# 1.net
KiCad netlist of a schematic drawn in Altium Designer
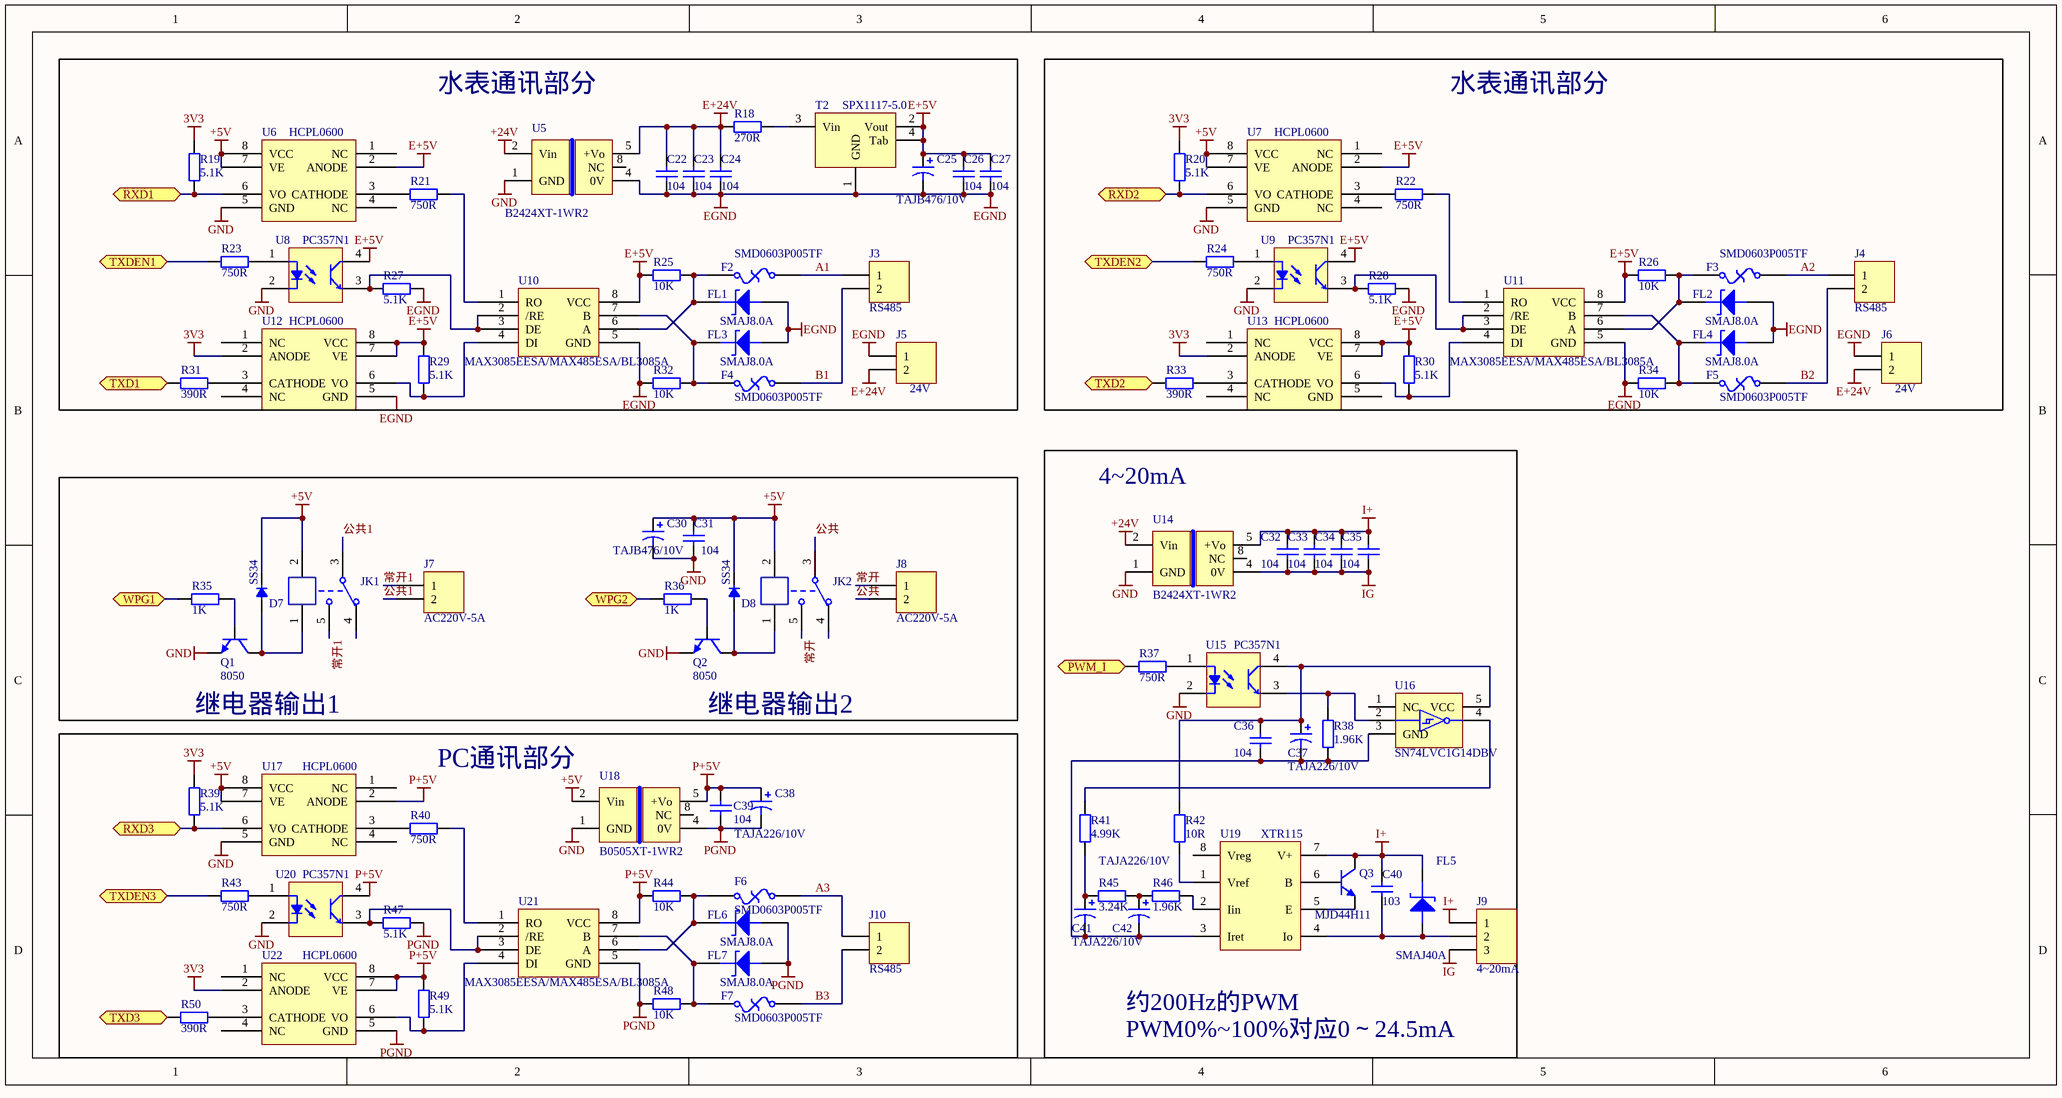
[diagram p0: 通讯部分(1).SchDoc]

(export (version "E")
  (design (tool "Eeschema 10.0.6"))
  (components
    (comp (ref "C22")
      (value "104")
      (footprint "C 0603_M")
      (description "Capacitor (Semiconductor SIM Model)")
      (fields (field (name "PUBLISHER") "Altium Limited"))
      (libsource (lib "*") (part "Cap Semi"))
    )
    (comp (ref "C23")
      (value "104")
      (footprint "C 0603_M")
      (description "Capacitor (Semiconductor SIM Model)")
      (fields (field (name "PUBLISHER") "Altium Limited"))
      (libsource (lib "*") (part "Cap Semi"))
    )
    (comp (ref "C24")
      (value "104")
      (footprint "C 0603_M")
      (description "Capacitor (Semiconductor SIM Model)")
      (fields (field (name "PUBLISHER") "Altium Limited"))
      (libsource (lib "*") (part "Cap Semi"))
    )
    (comp (ref "C25")
      (value "TAJB476/10V")
      (footprint "3528")
      (description "Polarized Capacitor (Radial)")
      (fields (field (name "PUBLISHER") "Altium Limited"))
      (libsource (lib "*") (part "Cap Pol1"))
    )
    (comp (ref "C26")
      (value "104")
      (footprint "C 0603_M")
      (description "Capacitor (Semiconductor SIM Model)")
      (fields (field (name "PUBLISHER") "Altium Limited"))
      (libsource (lib "*") (part "Cap Semi"))
    )
    (comp (ref "C27")
      (value "104")
      (footprint "C 0603_M")
      (description "Capacitor (Semiconductor SIM Model)")
      (fields (field (name "PUBLISHER") "Altium Limited"))
      (libsource (lib "*") (part "Cap Semi"))
    )
    (comp (ref "C30")
      (value "TAJB476/10V")
      (footprint "3528")
      (description "Polarized Capacitor (Radial)")
      (fields (field (name "PUBLISHER") "Altium Limited"))
      (libsource (lib "*") (part "Cap Pol1"))
    )
    (comp (ref "C31")
      (value "104")
      (footprint "C 0603_M")
      (description "Capacitor (Semiconductor SIM Model)")
      (fields (field (name "PUBLISHER") "Altium Limited"))
      (libsource (lib "*") (part "Cap Semi"))
    )
    (comp (ref "C32")
      (value "104")
      (footprint "C 0603_M")
      (description "Capacitor (Semiconductor SIM Model)")
      (fields (field (name "PUBLISHER") "Altium Limited"))
      (libsource (lib "*") (part "Cap Semi"))
    )
    (comp (ref "C33")
      (value "104")
      (footprint "C 0603_M")
      (description "Capacitor (Semiconductor SIM Model)")
      (fields (field (name "PUBLISHER") "Altium Limited"))
      (libsource (lib "*") (part "Cap Semi"))
    )
    (comp (ref "C34")
      (value "104")
      (footprint "C 0603_M")
      (description "Capacitor (Semiconductor SIM Model)")
      (fields (field (name "PUBLISHER") "Altium Limited"))
      (libsource (lib "*") (part "Cap Semi"))
    )
    (comp (ref "C35")
      (value "104")
      (footprint "C 0603_M")
      (description "Capacitor (Semiconductor SIM Model)")
      (fields (field (name "PUBLISHER") "Altium Limited"))
      (libsource (lib "*") (part "Cap Semi"))
    )
    (comp (ref "C36")
      (value "104")
      (footprint "C 0603_M")
      (description "Capacitor (Semiconductor SIM Model)")
      (fields (field (name "PUBLISHER") "Altium Limited"))
      (libsource (lib "*") (part "Cap Semi"))
    )
    (comp (ref "C37")
      (value "TAJA226/10V")
      (footprint "3216")
      (description "Polarized Capacitor (Radial)")
      (fields (field (name "PUBLISHER") "Altium Limited"))
      (libsource (lib "*") (part "Cap Pol1"))
    )
    (comp (ref "C38")
      (value "TAJA226/10V")
      (footprint "3216")
      (description "Polarized Capacitor (Radial)")
      (fields (field (name "PUBLISHER") "Altium Limited"))
      (libsource (lib "*") (part "Cap Pol1"))
    )
    (comp (ref "C39")
      (value "104")
      (footprint "C 0603_M")
      (description "Capacitor (Semiconductor SIM Model)")
      (fields (field (name "PUBLISHER") "Altium Limited"))
      (libsource (lib "*") (part "Cap Semi"))
    )
    (comp (ref "C40")
      (value "103")
      (footprint "C 0603_M")
      (description "Capacitor (Semiconductor SIM Model)")
      (fields (field (name "PUBLISHER") "Altium Limited"))
      (libsource (lib "*") (part "Cap Semi"))
    )
    (comp (ref "C41")
      (value "TAJA226/10V")
      (footprint "3216")
      (description "Polarized Capacitor (Radial)")
      (fields (field (name "PUBLISHER") "Altium Limited"))
      (libsource (lib "*") (part "Cap Pol1"))
    )
    (comp (ref "C42")
      (value "TAJA226/10V")
      (footprint "3216")
      (description "Polarized Capacitor (Radial)")
      (fields (field (name "PUBLISHER") "Altium Limited"))
      (libsource (lib "*") (part "Cap Pol1"))
    )
    (comp (ref "D7")
      (value "SS34")
      (footprint "SMA")
      (fields (field (name "PUBLISHER") "Altium Limited"))
      (libsource (lib "史福祥库") (part "D"))
    )
    (comp (ref "D8")
      (value "SS34")
      (footprint "SMA")
      (fields (field (name "PUBLISHER") "Altium Limited"))
      (libsource (lib "史福祥库") (part "D"))
    )
    (comp (ref "F2")
      (value "SMD0603P005TF")
      (footprint "R 0603_M")
      (description "Thermal Fuse")
      (fields (field (name "PUBLISHER") "50mA"))
      (libsource (lib "communication_Project1") (part "Fuse Thermal"))
    )
    (comp (ref "F3")
      (value "SMD0603P005TF")
      (footprint "R 0603_M")
      (description "Thermal Fuse")
      (fields (field (name "PUBLISHER") "50mA"))
      (libsource (lib "communication_Project1") (part "Fuse Thermal"))
    )
    (comp (ref "F4")
      (value "SMD0603P005TF")
      (footprint "R 0603_M")
      (description "Thermal Fuse")
      (fields (field (name "PUBLISHER") "50mA"))
      (libsource (lib "communication_Project1") (part "Fuse Thermal"))
    )
    (comp (ref "F5")
      (value "SMD0603P005TF")
      (footprint "R 0603_M")
      (description "Thermal Fuse")
      (fields (field (name "PUBLISHER") "50mA"))
      (libsource (lib "communication_Project1") (part "Fuse Thermal"))
    )
    (comp (ref "F6")
      (value "SMD0603P005TF")
      (footprint "R 0603_M")
      (description "Thermal Fuse")
      (fields (field (name "PUBLISHER") "50mA"))
      (libsource (lib "communication_Project1") (part "Fuse Thermal"))
    )
    (comp (ref "F7")
      (value "SMD0603P005TF")
      (footprint "R 0603_M")
      (description "Thermal Fuse")
      (fields (field (name "PUBLISHER") "50mA"))
      (libsource (lib "communication_Project1") (part "Fuse Thermal"))
    )
    (comp (ref "FL1")
      (value "SMAJ8.0A")
      (footprint "SMA")
      (description "Zener Diode")
      (libsource (lib "*") (part "ZENER2"))
    )
    (comp (ref "FL2")
      (value "SMAJ8.0A")
      (footprint "SMA")
      (description "Zener Diode")
      (libsource (lib "*") (part "ZENER2"))
    )
    (comp (ref "FL3")
      (value "SMAJ8.0A")
      (footprint "SMA")
      (description "Zener Diode")
      (libsource (lib "*") (part "ZENER2"))
    )
    (comp (ref "FL4")
      (value "SMAJ8.0A")
      (footprint "SMA")
      (description "Zener Diode")
      (libsource (lib "*") (part "ZENER2"))
    )
    (comp (ref "FL5")
      (value "SMAJ40A")
      (footprint "SMA")
      (description "Zener Diode")
      (libsource (lib "YYL") (part "ZENER2"))
    )
    (comp (ref "FL6")
      (value "SMAJ8.0A")
      (footprint "SMA")
      (description "Zener Diode")
      (libsource (lib "*") (part "ZENER2"))
    )
    (comp (ref "FL7")
      (value "SMAJ8.0A")
      (footprint "SMA")
      (description "Zener Diode")
      (libsource (lib "*") (part "ZENER2"))
    )
    (comp (ref "J3")
      (value "RS485")
      (footprint "KF128-5.08-2P")
      (description "Header, 2-Pin")
      (fields (field (name "PUBLISHER") "Altium Limited"))
      (libsource (lib "Miscellaneous Connectors") (part "Header 2"))
    )
    (comp (ref "J4")
      (value "RS485")
      (footprint "KF128-5.08-2P")
      (description "Header, 2-Pin")
      (fields (field (name "PUBLISHER") "Altium Limited"))
      (libsource (lib "Miscellaneous Connectors") (part "Header 2"))
    )
    (comp (ref "J5")
      (value "24V")
      (footprint "KF128-5.08-2P")
      (description "Header, 2-Pin")
      (fields (field (name "PUBLISHER") "Altium Limited"))
      (libsource (lib "Miscellaneous Connectors") (part "Header 2"))
    )
    (comp (ref "J6")
      (value "24V")
      (footprint "KF128-5.08-2P")
      (description "Header, 2-Pin")
      (fields (field (name "PUBLISHER") "Altium Limited"))
      (libsource (lib "Miscellaneous Connectors") (part "Header 2"))
    )
    (comp (ref "J7")
      (value "AC220V-5A")
      (footprint "KF128-5.08-2P")
      (description "Header, 2-Pin")
      (fields (field (name "PUBLISHER") "Altium Limited"))
      (libsource (lib "Miscellaneous Connectors") (part "Header 2"))
    )
    (comp (ref "J8")
      (value "AC220V-5A")
      (footprint "KF128-5.08-2P")
      (description "Header, 2-Pin")
      (fields (field (name "PUBLISHER") "Altium Limited"))
      (libsource (lib "Miscellaneous Connectors") (part "Header 2"))
    )
    (comp (ref "J9")
      (value "4~20mA")
      (footprint "KF128-5.08-3P")
      (description "Header, 3-Pin")
      (fields (field (name "PUBLISHER") "Altium Limited"))
      (libsource (lib "Miscellaneous Connectors") (part "Header 3"))
    )
    (comp (ref "J10")
      (value "RS485")
      (footprint "KF128-5.08-2P")
      (description "Header, 2-Pin")
      (fields (field (name "PUBLISHER") "Altium Limited"))
      (libsource (lib "Miscellaneous Connectors") (part "Header 2"))
    )
    (comp (ref "JK1")
      (value "~")
      (footprint "SRD-C_B")
      (description "5V单路双控继电器")
      (fields (field (name "版权归属") "源创客"))
      (libsource (lib "继电器") (part "SRD-05VDC-SL-C"))
    )
    (comp (ref "JK2")
      (value "~")
      (footprint "SRD-C_B")
      (description "5V单路双控继电器")
      (fields (field (name "版权归属") "源创客"))
      (libsource (lib "继电器") (part "SRD-05VDC-SL-C"))
    )
    (comp (ref "Q1") (value "8050") (footprint "SOT-23") (libsource (lib "史福祥库") (part "NPN")))
    (comp (ref "Q2") (value "8050") (footprint "SOT-23") (libsource (lib "史福祥库") (part "NPN")))
    (comp (ref "Q3")
      (value "MJD44H11")
      (footprint "DPAK")
      (description "NPN Bipolar Transistor")
      (fields (field (name "PUBLISHER") "Altium Limited"))
      (libsource (lib "YYL") (part "MJD44H11"))
    )
    (comp (ref "R18")
      (value "270R")
      (footprint "R 1206_M")
      (description "Resistor")
      (fields (field (name "PUBLISHER") "Altium Limited"))
      (libsource (lib "") (part "Res2_3"))
    )
    (comp (ref "R19")
      (value "5.1K")
      (footprint "R 0603_M")
      (description "Resistor")
      (fields (field (name "PUBLISHER") "Altium Limited"))
      (libsource (lib "") (part "Res2_1"))
    )
    (comp (ref "R20")
      (value "5.1K")
      (footprint "R 0603_M")
      (description "Resistor")
      (fields (field (name "PUBLISHER") "Altium Limited"))
      (libsource (lib "") (part "Res2_1"))
    )
    (comp (ref "R21")
      (value "750R")
      (footprint "R 0603_M")
      (description "Resistor")
      (fields (field (name "PUBLISHER") "Altium Limited"))
      (libsource (lib "*") (part "Res2"))
    )
    (comp (ref "R22")
      (value "750R")
      (footprint "R 0603_M")
      (description "Resistor")
      (fields (field (name "PUBLISHER") "Altium Limited"))
      (libsource (lib "*") (part "Res2"))
    )
    (comp (ref "R23")
      (value "750R")
      (footprint "R 0603_M")
      (description "Resistor")
      (fields (field (name "PUBLISHER") "Altium Limited"))
      (libsource (lib "*") (part "Res2"))
    )
    (comp (ref "R24")
      (value "750R")
      (footprint "R 0603_M")
      (description "Resistor")
      (fields (field (name "PUBLISHER") "Altium Limited"))
      (libsource (lib "*") (part "Res2"))
    )
    (comp (ref "R25")
      (value "10K")
      (footprint "R 0603_M")
      (description "Resistor")
      (fields (field (name "PUBLISHER") "Altium Limited"))
      (libsource (lib "") (part "Res2_3"))
    )
    (comp (ref "R26")
      (value "10K")
      (footprint "R 0603_M")
      (description "Resistor")
      (fields (field (name "PUBLISHER") "Altium Limited"))
      (libsource (lib "") (part "Res2_3"))
    )
    (comp (ref "R27")
      (value "5.1K")
      (footprint "R 0603_M")
      (description "Resistor")
      (fields (field (name "PUBLISHER") "Altium Limited"))
      (libsource (lib "*") (part "Res2"))
    )
    (comp (ref "R28")
      (value "5.1K")
      (footprint "R 0603_M")
      (description "Resistor")
      (fields (field (name "PUBLISHER") "Altium Limited"))
      (libsource (lib "*") (part "Res2"))
    )
    (comp (ref "R29")
      (value "5.1K")
      (footprint "R 0603_M")
      (description "Resistor")
      (fields (field (name "PUBLISHER") "Altium Limited"))
      (libsource (lib "") (part "Res2_1"))
    )
    (comp (ref "R30")
      (value "5.1K")
      (footprint "R 0603_M")
      (description "Resistor")
      (fields (field (name "PUBLISHER") "Altium Limited"))
      (libsource (lib "") (part "Res2_1"))
    )
    (comp (ref "R31")
      (value "390R")
      (footprint "R 0603_M")
      (description "Resistor")
      (fields (field (name "PUBLISHER") "Altium Limited"))
      (libsource (lib "*") (part "Res2"))
    )
    (comp (ref "R32")
      (value "10K")
      (footprint "R 0603_M")
      (description "Resistor")
      (fields (field (name "PUBLISHER") "Altium Limited"))
      (libsource (lib "") (part "Res2_3"))
    )
    (comp (ref "R33")
      (value "390R")
      (footprint "R 0603_M")
      (description "Resistor")
      (fields (field (name "PUBLISHER") "Altium Limited"))
      (libsource (lib "*") (part "Res2"))
    )
    (comp (ref "R34")
      (value "10K")
      (footprint "R 0603_M")
      (description "Resistor")
      (fields (field (name "PUBLISHER") "Altium Limited"))
      (libsource (lib "") (part "Res2_3"))
    )
    (comp (ref "R35")
      (value "1K")
      (footprint "R 0603_M")
      (description "Resistor")
      (fields (field (name "PUBLISHER") "Altium Limited"))
      (libsource (lib "*") (part "Res2"))
    )
    (comp (ref "R36")
      (value "1K")
      (footprint "R 0603_M")
      (description "Resistor")
      (fields (field (name "PUBLISHER") "Altium Limited"))
      (libsource (lib "*") (part "Res2"))
    )
    (comp (ref "R37")
      (value "750R")
      (footprint "R 0603_M")
      (description "Resistor")
      (fields (field (name "PUBLISHER") "Altium Limited"))
      (libsource (lib "*") (part "Res2"))
    )
    (comp (ref "R38")
      (value "1.96K")
      (footprint "R 0603_M")
      (description "Resistor")
      (fields (field (name "PUBLISHER") "Altium Limited"))
      (libsource (lib "") (part "Res2_2"))
    )
    (comp (ref "R39")
      (value "5.1K")
      (footprint "R 0603_M")
      (description "Resistor")
      (fields (field (name "PUBLISHER") "Altium Limited"))
      (libsource (lib "") (part "Res2_1"))
    )
    (comp (ref "R40")
      (value "750R")
      (footprint "R 0603_M")
      (description "Resistor")
      (fields (field (name "PUBLISHER") "Altium Limited"))
      (libsource (lib "*") (part "Res2"))
    )
    (comp (ref "R41")
      (value "4.99K")
      (footprint "R 0603_M")
      (description "Resistor")
      (fields (field (name "PUBLISHER") "Altium Limited"))
      (libsource (lib "") (part "Res2_2"))
    )
    (comp (ref "R42")
      (value "10R")
      (footprint "R 0603_M")
      (description "Resistor")
      (fields (field (name "PUBLISHER") "Altium Limited"))
      (libsource (lib "") (part "Res2_2"))
    )
    (comp (ref "R43")
      (value "750R")
      (footprint "R 0603_M")
      (description "Resistor")
      (fields (field (name "PUBLISHER") "Altium Limited"))
      (libsource (lib "*") (part "Res2"))
    )
    (comp (ref "R44")
      (value "10K")
      (footprint "R 0603_M")
      (description "Resistor")
      (fields (field (name "PUBLISHER") "Altium Limited"))
      (libsource (lib "") (part "Res2_3"))
    )
    (comp (ref "R45")
      (value "3.24K")
      (footprint "R 0603_M")
      (description "Resistor")
      (fields (field (name "PUBLISHER") "Altium Limited"))
      (libsource (lib "*") (part "Res2"))
    )
    (comp (ref "R46")
      (value "1.96K")
      (footprint "R 0603_M")
      (description "Resistor")
      (fields (field (name "PUBLISHER") "Altium Limited"))
      (libsource (lib "*") (part "Res2"))
    )
    (comp (ref "R47")
      (value "5.1K")
      (footprint "R 0603_M")
      (description "Resistor")
      (fields (field (name "PUBLISHER") "Altium Limited"))
      (libsource (lib "*") (part "Res2"))
    )
    (comp (ref "R48")
      (value "10K")
      (footprint "R 0603_M")
      (description "Resistor")
      (fields (field (name "PUBLISHER") "Altium Limited"))
      (libsource (lib "") (part "Res2_3"))
    )
    (comp (ref "R49")
      (value "5.1K")
      (footprint "R 0603_M")
      (description "Resistor")
      (fields (field (name "PUBLISHER") "Altium Limited"))
      (libsource (lib "") (part "Res2_1"))
    )
    (comp (ref "R50")
      (value "390R")
      (footprint "R 0603_M")
      (description "Resistor")
      (fields (field (name "PUBLISHER") "Altium Limited"))
      (libsource (lib "*") (part "Res2"))
    )
    (comp (ref "T2") (value "SPX1117-5.0") (footprint "SOT-223") (libsource (lib "YYL") (part "1117")))
    (comp (ref "U5") (value "B2424XT-1WR2") (footprint "B_XT-1W") (libsource (lib "YYL") (part "B_XT-1W")))
    (comp (ref "U6") (value "HCPL0600") (footprint "SO-8") (libsource (lib "*") (part "6N137")))
    (comp (ref "U7") (value "HCPL0600") (footprint "SO-8") (libsource (lib "*") (part "6N137")))
    (comp (ref "U8") (value "PC357N1") (footprint "PC357") (libsource (lib "YYL") (part "TLP521-1")))
    (comp (ref "U9") (value "PC357N1") (footprint "PC357") (libsource (lib "YYL") (part "TLP521-1")))
    (comp (ref "U10")
      (value "MAX3085EESA/MAX485ESA/BL3085A")
      (footprint "SO-8")
      (libsource (lib "communication_Project1") (part "MAX485"))
    )
    (comp (ref "U11")
      (value "MAX3085EESA/MAX485ESA/BL3085A")
      (footprint "SO-8")
      (libsource (lib "communication_Project1") (part "MAX485"))
    )
    (comp (ref "U12") (value "HCPL0600") (footprint "SO-8") (libsource (lib "") (part "6N137_1")))
    (comp (ref "U13") (value "HCPL0600") (footprint "SO-8") (libsource (lib "") (part "6N137_1")))
    (comp (ref "U14") (value "B2424XT-1WR2") (footprint "B_XT-1W") (libsource (lib "YYL") (part "B_XT-1W")))
    (comp (ref "U15") (value "PC357N1") (footprint "PC357") (libsource (lib "YYL") (part "TLP521-1")))
    (comp (ref "U16")
      (value "SN74LVC1G14DBV")
      (footprint "SOT23-5")
      (libsource (lib "YYL") (part "SN74LVC1G14DBV"))
    )
    (comp (ref "U17") (value "HCPL0600") (footprint "SO-8") (libsource (lib "*") (part "6N137")))
    (comp (ref "U18") (value "B0505XT-1WR2") (footprint "B_XT-1W") (libsource (lib "YYL") (part "B_XT-1W")))
    (comp (ref "U19") (value "XTR115") (footprint "SO-8") (libsource (lib "YYL") (part "XTR115")))
    (comp (ref "U20") (value "PC357N1") (footprint "PC357") (libsource (lib "YYL") (part "TLP521-1")))
    (comp (ref "U21")
      (value "MAX3085EESA/MAX485ESA/BL3085A")
      (footprint "SO-8")
      (libsource (lib "communication_Project1") (part "MAX485"))
    )
    (comp (ref "U22") (value "HCPL0600") (footprint "SO-8") (libsource (lib "") (part "6N137_1")))
  )
  (nets
    (net (code "1") (name "+5V") (class "Default")
      (node (ref "C30") (pin "1") (pinfunction "1_1") (pintype "passive"))
      (node (ref "C31") (pin "2") (pinfunction "2_2") (pintype "passive"))
      (node (ref "D7") (pin "2") (pinfunction "2_2") (pintype "passive"))
      (node (ref "D8") (pin "2") (pinfunction "2_2") (pintype "passive"))
      (node (ref "JK1") (pin "2") (pinfunction "2_2") (pintype "passive"))
      (node (ref "JK2") (pin "2") (pinfunction "2_2") (pintype "passive"))
      (node (ref "U17") (pin "7") (pinfunction "VE_7") (pintype "passive"))
      (node (ref "U17") (pin "8") (pinfunction "VCC_8") (pintype "passive"))
      (node (ref "U18") (pin "2") (pinfunction "Vin_2") (pintype "passive"))
      (node (ref "U6") (pin "7") (pinfunction "VE_7") (pintype "passive"))
      (node (ref "U6") (pin "8") (pinfunction "VCC_8") (pintype "passive"))
      (node (ref "U7") (pin "7") (pinfunction "VE_7") (pintype "passive"))
      (node (ref "U7") (pin "8") (pinfunction "VCC_8") (pintype "passive"))
    )
    (net (code "2") (name "+24V") (class "Default")
      (node (ref "U14") (pin "2") (pinfunction "Vin_2") (pintype "passive"))
      (node (ref "U5") (pin "2") (pinfunction "Vin_2") (pintype "passive"))
    )
    (net (code "3") (name "/A1") (class "Default")
      (node (ref "F2") (pin "1") (pinfunction "1_1") (pintype "passive"))
      (node (ref "J3") (pin "1") (pinfunction "1_1") (pintype "passive"))
    )
    (net (code "4") (name "/A2") (class "Default")
      (node (ref "F3") (pin "1") (pinfunction "1_1") (pintype "passive"))
      (node (ref "J4") (pin "1") (pinfunction "1_1") (pintype "passive"))
    )
    (net (code "5") (name "/A3") (class "Default")
      (node (ref "F6") (pin "1") (pinfunction "1_1") (pintype "passive"))
      (node (ref "J10") (pin "1") (pinfunction "1_1") (pintype "passive"))
    )
    (net (code "6") (name "/B1") (class "Default")
      (node (ref "F4") (pin "1") (pinfunction "1_1") (pintype "passive"))
      (node (ref "J3") (pin "2") (pinfunction "2_2") (pintype "passive"))
    )
    (net (code "7") (name "/B2") (class "Default")
      (node (ref "F5") (pin "1") (pinfunction "1_1") (pintype "passive"))
      (node (ref "J4") (pin "2") (pinfunction "2_2") (pintype "passive"))
    )
    (net (code "8") (name "/B3") (class "Default")
      (node (ref "F7") (pin "1") (pinfunction "1_1") (pintype "passive"))
      (node (ref "J10") (pin "2") (pinfunction "2_2") (pintype "passive"))
    )
    (net (code "9") (name "/PWM_I") (class "Default")
      (node (ref "R37") (pin "1") (pinfunction "1_1") (pintype "passive"))
    )
    (net (code "10") (name "/RXD1") (class "Default")
      (node (ref "R19") (pin "1") (pinfunction "1_1") (pintype "passive"))
      (node (ref "U6") (pin "6") (pinfunction "VO_6") (pintype "passive"))
    )
    (net (code "11") (name "/RXD2") (class "Default")
      (node (ref "R20") (pin "1") (pinfunction "1_1") (pintype "passive"))
      (node (ref "U7") (pin "6") (pinfunction "VO_6") (pintype "passive"))
    )
    (net (code "12") (name "/RXD3") (class "Default")
      (node (ref "R39") (pin "1") (pinfunction "1_1") (pintype "passive"))
      (node (ref "U17") (pin "6") (pinfunction "VO_6") (pintype "passive"))
    )
    (net (code "13") (name "/TXD1") (class "Default")
      (node (ref "R31") (pin "1") (pinfunction "1_1") (pintype "passive"))
    )
    (net (code "14") (name "/TXD2") (class "Default")
      (node (ref "R33") (pin "1") (pinfunction "1_1") (pintype "passive"))
    )
    (net (code "15") (name "/TXD3") (class "Default")
      (node (ref "R50") (pin "1") (pinfunction "1_1") (pintype "passive"))
    )
    (net (code "16") (name "/TXDEN1") (class "Default")
      (node (ref "R23") (pin "1") (pinfunction "1_1") (pintype "passive"))
    )
    (net (code "17") (name "/TXDEN2") (class "Default")
      (node (ref "R24") (pin "1") (pinfunction "1_1") (pintype "passive"))
    )
    (net (code "18") (name "/TXDEN3") (class "Default")
      (node (ref "R43") (pin "1") (pinfunction "1_1") (pintype "passive"))
    )
    (net (code "19") (name "/WPG1") (class "Default")
      (node (ref "R35") (pin "1") (pinfunction "1_1") (pintype "passive"))
    )
    (net (code "20") (name "/WPG2") (class "Default")
      (node (ref "R36") (pin "1") (pinfunction "1_1") (pintype "passive"))
    )
    (net (code "21") (name "/公共") (class "Default")
      (node (ref "J8") (pin "2") (pinfunction "2_2") (pintype "passive"))
      (node (ref "JK2") (pin "3") (pinfunction "3_3") (pintype "passive"))
    )
    (net (code "22") (name "/公共1") (class "Default")
      (node (ref "J7") (pin "2") (pinfunction "2_2") (pintype "passive"))
      (node (ref "JK1") (pin "3") (pinfunction "3_3") (pintype "passive"))
    )
    (net (code "23") (name "/常开") (class "Default")
      (node (ref "J8") (pin "1") (pinfunction "1_1") (pintype "passive"))
      (node (ref "JK2") (pin "5") (pinfunction "5_5") (pintype "passive"))
    )
    (net (code "24") (name "/常开1") (class "Default")
      (node (ref "J7") (pin "1") (pinfunction "1_1") (pintype "passive"))
      (node (ref "JK1") (pin "5") (pinfunction "5_5") (pintype "passive"))
    )
    (net (code "25") (name "3V3") (class "Default")
      (node (ref "R19") (pin "2") (pinfunction "2_2") (pintype "passive"))
      (node (ref "R20") (pin "2") (pinfunction "2_2") (pintype "passive"))
      (node (ref "R39") (pin "2") (pinfunction "2_2") (pintype "passive"))
      (node (ref "U12") (pin "2") (pinfunction "ANODE_2") (pintype "passive"))
      (node (ref "U13") (pin "2") (pinfunction "ANODE_2") (pintype "passive"))
      (node (ref "U22") (pin "2") (pinfunction "ANODE_2") (pintype "passive"))
    )
    (net (code "26") (name "E+5V") (class "Default")
      (node (ref "C25") (pin "1") (pinfunction "1_1") (pintype "passive"))
      (node (ref "C26") (pin "2") (pinfunction "2_2") (pintype "passive"))
      (node (ref "C27") (pin "2") (pinfunction "2_2") (pintype "passive"))
      (node (ref "R25") (pin "2") (pinfunction "2_2") (pintype "passive"))
      (node (ref "R26") (pin "2") (pinfunction "2_2") (pintype "passive"))
      (node (ref "R29") (pin "2") (pinfunction "2_2") (pintype "passive"))
      (node (ref "R30") (pin "2") (pinfunction "2_2") (pintype "passive"))
      (node (ref "T2") (pin "2") (pinfunction "Vout_2") (pintype "passive"))
      (node (ref "T2") (pin "4") (pinfunction "Tab_4") (pintype "passive"))
      (node (ref "U10") (pin "8") (pinfunction "VCC_8") (pintype "power_in"))
      (node (ref "U11") (pin "8") (pinfunction "VCC_8") (pintype "power_in"))
      (node (ref "U12") (pin "7") (pinfunction "VE_7") (pintype "passive"))
      (node (ref "U12") (pin "8") (pinfunction "VCC_8") (pintype "passive"))
      (node (ref "U13") (pin "7") (pinfunction "VE_7") (pintype "passive"))
      (node (ref "U13") (pin "8") (pinfunction "VCC_8") (pintype "passive"))
      (node (ref "U6") (pin "2") (pinfunction "ANODE_2") (pintype "passive"))
      (node (ref "U7") (pin "2") (pinfunction "ANODE_2") (pintype "passive"))
      (node (ref "U8") (pin "4") (pintype "passive"))
      (node (ref "U9") (pin "4") (pintype "passive"))
    )
    (net (code "27") (name "E+24V") (class "Default")
      (node (ref "C22") (pin "2") (pinfunction "2_2") (pintype "passive"))
      (node (ref "C23") (pin "2") (pinfunction "2_2") (pintype "passive"))
      (node (ref "C24") (pin "2") (pinfunction "2_2") (pintype "passive"))
      (node (ref "J5") (pin "2") (pinfunction "2_2") (pintype "passive"))
      (node (ref "J6") (pin "2") (pinfunction "2_2") (pintype "passive"))
      (node (ref "R18") (pin "2") (pinfunction "2_2") (pintype "passive"))
      (node (ref "U5") (pin "5") (pinfunction "+Vo_5") (pintype "passive"))
    )
    (net (code "28") (name "EGND") (class "Default")
      (node (ref "C22") (pin "1") (pinfunction "1_1") (pintype "passive"))
      (node (ref "C23") (pin "1") (pinfunction "1_1") (pintype "passive"))
      (node (ref "C24") (pin "1") (pinfunction "1_1") (pintype "passive"))
      (node (ref "C25") (pin "2") (pinfunction "2_2") (pintype "passive"))
      (node (ref "C26") (pin "1") (pinfunction "1_1") (pintype "passive"))
      (node (ref "C27") (pin "1") (pinfunction "1_1") (pintype "passive"))
      (node (ref "FL1") (pin "1") (pinfunction "A_1") (pintype "passive"))
      (node (ref "FL2") (pin "1") (pinfunction "A_1") (pintype "passive"))
      (node (ref "FL3") (pin "1") (pinfunction "A_1") (pintype "passive"))
      (node (ref "FL4") (pin "1") (pinfunction "A_1") (pintype "passive"))
      (node (ref "J5") (pin "1") (pinfunction "1_1") (pintype "passive"))
      (node (ref "J6") (pin "1") (pinfunction "1_1") (pintype "passive"))
      (node (ref "R27") (pin "2") (pinfunction "2_2") (pintype "passive"))
      (node (ref "R28") (pin "2") (pinfunction "2_2") (pintype "passive"))
      (node (ref "R32") (pin "2") (pinfunction "2_2") (pintype "passive"))
      (node (ref "R34") (pin "2") (pinfunction "2_2") (pintype "passive"))
      (node (ref "T2") (pin "1") (pinfunction "GND_1") (pintype "passive"))
      (node (ref "U10") (pin "5") (pinfunction "GND_5") (pintype "passive"))
      (node (ref "U11") (pin "5") (pinfunction "GND_5") (pintype "passive"))
      (node (ref "U12") (pin "5") (pinfunction "GND_5") (pintype "passive"))
      (node (ref "U5") (pin "4") (pinfunction "0V_4") (pintype "passive"))
    )
    (net (code "29") (name "GND") (class "Default")
      (node (ref "C30") (pin "2") (pinfunction "2_2") (pintype "passive"))
      (node (ref "C31") (pin "1") (pinfunction "1_1") (pintype "passive"))
      (node (ref "Q1") (pin "2") (pinfunction "E_2") (pintype "passive"))
      (node (ref "Q2") (pin "2") (pinfunction "E_2") (pintype "passive"))
      (node (ref "U14") (pin "1") (pinfunction "GND_1") (pintype "passive"))
      (node (ref "U15") (pin "2") (pintype "passive"))
      (node (ref "U17") (pin "5") (pinfunction "GND_5") (pintype "passive"))
      (node (ref "U18") (pin "1") (pinfunction "GND_1") (pintype "passive"))
      (node (ref "U20") (pin "2") (pintype "passive"))
      (node (ref "U5") (pin "1") (pinfunction "GND_1") (pintype "passive"))
      (node (ref "U6") (pin "5") (pinfunction "GND_5") (pintype "passive"))
      (node (ref "U7") (pin "5") (pinfunction "GND_5") (pintype "passive"))
      (node (ref "U8") (pin "2") (pintype "passive"))
      (node (ref "U9") (pin "2") (pintype "passive"))
    )
    (net (code "30") (name "I+") (class "Default")
      (node (ref "C32") (pin "2") (pinfunction "2_2") (pintype "passive"))
      (node (ref "C33") (pin "2") (pinfunction "2_2") (pintype "passive"))
      (node (ref "C34") (pin "2") (pinfunction "2_2") (pintype "passive"))
      (node (ref "C35") (pin "2") (pinfunction "2_2") (pintype "passive"))
      (node (ref "C40") (pin "2") (pinfunction "2_2") (pintype "passive"))
      (node (ref "FL5") (pin "2") (pinfunction "K_2") (pintype "passive"))
      (node (ref "J9") (pin "1") (pinfunction "1_1") (pintype "passive"))
      (node (ref "Q3") (pin "2") (pinfunction "C_2") (pintype "passive"))
      (node (ref "U14") (pin "5") (pinfunction "+Vo_5") (pintype "passive"))
      (node (ref "U19") (pin "7") (pinfunction "V+_7") (pintype "passive"))
    )
    (net (code "31") (name "IG") (class "Default")
      (node (ref "C32") (pin "1") (pinfunction "1_1") (pintype "passive"))
      (node (ref "C33") (pin "1") (pinfunction "1_1") (pintype "passive"))
      (node (ref "C34") (pin "1") (pinfunction "1_1") (pintype "passive"))
      (node (ref "C35") (pin "1") (pinfunction "1_1") (pintype "passive"))
      (node (ref "J9") (pin "3") (pinfunction "3_3") (pintype "passive"))
      (node (ref "U14") (pin "4") (pinfunction "0V_4") (pintype "passive"))
    )
    (net (code "32") (name "Net-(C41-Pad1)") (class "Default")
      (node (ref "C41") (pin "1") (pinfunction "1_1") (pintype "passive"))
      (node (ref "R41") (pin "1") (pinfunction "1_1") (pintype "passive"))
      (node (ref "R45") (pin "1") (pinfunction "1_1") (pintype "passive"))
    )
    (net (code "33") (name "Net-(C42-Pad1)") (class "Default")
      (node (ref "C42") (pin "1") (pinfunction "1_1") (pintype "passive"))
      (node (ref "R45") (pin "2") (pinfunction "2_2") (pintype "passive"))
      (node (ref "R46") (pin "1") (pinfunction "1_1") (pintype "passive"))
    )
    (net (code "34") (name "Net-(FL1-K)") (class "Default")
      (node (ref "F2") (pin "2") (pinfunction "2_2") (pintype "passive"))
      (node (ref "FL1") (pin "2") (pinfunction "K_2") (pintype "passive"))
      (node (ref "R25") (pin "1") (pinfunction "1_1") (pintype "passive"))
      (node (ref "U10") (pin "6") (pinfunction "A_6") (pintype "passive"))
    )
    (net (code "35") (name "Net-(FL2-K)") (class "Default")
      (node (ref "F3") (pin "2") (pinfunction "2_2") (pintype "passive"))
      (node (ref "FL2") (pin "2") (pinfunction "K_2") (pintype "passive"))
      (node (ref "R26") (pin "1") (pinfunction "1_1") (pintype "passive"))
      (node (ref "U11") (pin "6") (pinfunction "A_6") (pintype "passive"))
    )
    (net (code "36") (name "Net-(FL3-K)") (class "Default")
      (node (ref "F4") (pin "2") (pinfunction "2_2") (pintype "passive"))
      (node (ref "FL3") (pin "2") (pinfunction "K_2") (pintype "passive"))
      (node (ref "R32") (pin "1") (pinfunction "1_1") (pintype "passive"))
      (node (ref "U10") (pin "7") (pinfunction "B_7") (pintype "passive"))
    )
    (net (code "37") (name "Net-(FL4-K)") (class "Default")
      (node (ref "F5") (pin "2") (pinfunction "2_2") (pintype "passive"))
      (node (ref "FL4") (pin "2") (pinfunction "K_2") (pintype "passive"))
      (node (ref "R34") (pin "1") (pinfunction "1_1") (pintype "passive"))
      (node (ref "U11") (pin "7") (pinfunction "B_7") (pintype "passive"))
    )
    (net (code "38") (name "Net-(FL5-A)") (class "Default")
      (node (ref "C40") (pin "1") (pinfunction "1_1") (pintype "passive"))
      (node (ref "FL5") (pin "1") (pinfunction "A_1") (pintype "passive"))
      (node (ref "J9") (pin "2") (pinfunction "2_2") (pintype "passive"))
      (node (ref "U19") (pin "4") (pinfunction "Io_4") (pintype "passive"))
    )
    (net (code "39") (name "Net-(FL6-K)") (class "Default")
      (node (ref "F6") (pin "2") (pinfunction "2_2") (pintype "passive"))
      (node (ref "FL6") (pin "2") (pinfunction "K_2") (pintype "passive"))
      (node (ref "R44") (pin "1") (pinfunction "1_1") (pintype "passive"))
      (node (ref "U21") (pin "6") (pinfunction "A_6") (pintype "passive"))
    )
    (net (code "40") (name "Net-(FL7-K)") (class "Default")
      (node (ref "F7") (pin "2") (pinfunction "2_2") (pintype "passive"))
      (node (ref "FL7") (pin "2") (pinfunction "K_2") (pintype "passive"))
      (node (ref "R48") (pin "1") (pinfunction "1_1") (pintype "passive"))
      (node (ref "U21") (pin "7") (pinfunction "B_7") (pintype "passive"))
    )
    (net (code "41") (name "Net-(Q1-B)") (class "Default")
      (node (ref "Q1") (pin "1") (pinfunction "B_1") (pintype "passive"))
      (node (ref "R35") (pin "2") (pinfunction "2_2") (pintype "passive"))
    )
    (net (code "42") (name "Net-(Q1-C)") (class "Default")
      (node (ref "D7") (pin "1") (pinfunction "1_1") (pintype "passive"))
      (node (ref "JK1") (pin "1") (pinfunction "1_1") (pintype "passive"))
      (node (ref "Q1") (pin "3") (pinfunction "C_3") (pintype "passive"))
    )
    (net (code "43") (name "Net-(Q2-B)") (class "Default")
      (node (ref "Q2") (pin "1") (pinfunction "B_1") (pintype "passive"))
      (node (ref "R36") (pin "2") (pinfunction "2_2") (pintype "passive"))
    )
    (net (code "44") (name "Net-(Q2-C)") (class "Default")
      (node (ref "D8") (pin "1") (pinfunction "1_1") (pintype "passive"))
      (node (ref "JK2") (pin "1") (pinfunction "1_1") (pintype "passive"))
      (node (ref "Q2") (pin "3") (pinfunction "C_3") (pintype "passive"))
    )
    (net (code "45") (name "Net-(Q3-B)") (class "Default")
      (node (ref "Q3") (pin "1") (pinfunction "B_1") (pintype "passive"))
      (node (ref "U19") (pin "6") (pinfunction "B_6") (pintype "passive"))
    )
    (net (code "46") (name "Net-(Q3-E)") (class "Default")
      (node (ref "Q3") (pin "3") (pinfunction "E_3") (pintype "passive"))
      (node (ref "U19") (pin "5") (pinfunction "E_5") (pintype "passive"))
    )
    (net (code "47") (name "Net-(R23-Pad2)") (class "Default")
      (node (ref "R23") (pin "2") (pinfunction "2_2") (pintype "passive"))
      (node (ref "U8") (pin "1") (pintype "passive"))
    )
    (net (code "48") (name "Net-(R24-Pad2)") (class "Default")
      (node (ref "R24") (pin "2") (pinfunction "2_2") (pintype "passive"))
      (node (ref "U9") (pin "1") (pintype "passive"))
    )
    (net (code "49") (name "Net-(R37-Pad2)") (class "Default")
      (node (ref "R37") (pin "2") (pinfunction "2_2") (pintype "passive"))
      (node (ref "U15") (pin "1") (pintype "passive"))
    )
    (net (code "50") (name "Net-(R38-Pad2)") (class "Default")
      (node (ref "R38") (pin "2") (pinfunction "2_2") (pintype "passive"))
      (node (ref "U15") (pin "3") (pintype "passive"))
      (node (ref "U16") (pin "2") (pintype "passive"))
    )
    (net (code "51") (name "Net-(R41-Pad2)") (class "Default")
      (node (ref "R41") (pin "2") (pinfunction "2_2") (pintype "passive"))
      (node (ref "U16") (pin "4") (pintype "passive"))
    )
    (net (code "52") (name "Net-(R43-Pad2)") (class "Default")
      (node (ref "R43") (pin "2") (pinfunction "2_2") (pintype "passive"))
      (node (ref "U20") (pin "1") (pintype "passive"))
    )
    (net (code "53") (name "Net-(T2-Vin)") (class "Default")
      (node (ref "R18") (pin "1") (pinfunction "1_1") (pintype "passive"))
      (node (ref "T2") (pin "3") (pinfunction "Vin_3") (pintype "passive"))
    )
    (net (code "54") (name "Net-(U6-CATHODE)") (class "Default")
      (node (ref "R21") (pin "1") (pinfunction "1_1") (pintype "passive"))
      (node (ref "U6") (pin "3") (pinfunction "CATHODE_3") (pintype "passive"))
    )
    (net (code "55") (name "Net-(U7-CATHODE)") (class "Default")
      (node (ref "R22") (pin "1") (pinfunction "1_1") (pintype "passive"))
      (node (ref "U7") (pin "3") (pinfunction "CATHODE_3") (pintype "passive"))
    )
    (net (code "56") (name "Net-(U10-DE)") (class "Default")
      (node (ref "R27") (pin "1") (pinfunction "1_1") (pintype "passive"))
      (node (ref "U10") (pin "2") (pinfunction "/RE_2") (pintype "passive"))
      (node (ref "U10") (pin "3") (pinfunction "DE_3") (pintype "passive"))
      (node (ref "U8") (pin "3") (pintype "passive"))
    )
    (net (code "57") (name "Net-(U10-DI)") (class "Default")
      (node (ref "R29") (pin "1") (pinfunction "1_1") (pintype "passive"))
      (node (ref "U10") (pin "4") (pinfunction "DI_4") (pintype "passive"))
      (node (ref "U12") (pin "6") (pinfunction "VO_6") (pintype "passive"))
    )
    (net (code "58") (name "Net-(U10-RO)") (class "Default")
      (node (ref "R21") (pin "2") (pinfunction "2_2") (pintype "passive"))
      (node (ref "U10") (pin "1") (pinfunction "RO_1") (pintype "passive"))
    )
    (net (code "59") (name "Net-(U11-DE)") (class "Default")
      (node (ref "R28") (pin "1") (pinfunction "1_1") (pintype "passive"))
      (node (ref "U11") (pin "2") (pinfunction "/RE_2") (pintype "passive"))
      (node (ref "U11") (pin "3") (pinfunction "DE_3") (pintype "passive"))
      (node (ref "U9") (pin "3") (pintype "passive"))
    )
    (net (code "60") (name "Net-(U11-DI)") (class "Default")
      (node (ref "R30") (pin "1") (pinfunction "1_1") (pintype "passive"))
      (node (ref "U11") (pin "4") (pinfunction "DI_4") (pintype "passive"))
      (node (ref "U13") (pin "6") (pinfunction "VO_6") (pintype "passive"))
    )
    (net (code "61") (name "Net-(U11-RO)") (class "Default")
      (node (ref "R22") (pin "2") (pinfunction "2_2") (pintype "passive"))
      (node (ref "U11") (pin "1") (pinfunction "RO_1") (pintype "passive"))
    )
    (net (code "62") (name "Net-(U12-CATHODE)") (class "Default")
      (node (ref "R31") (pin "2") (pinfunction "2_2") (pintype "passive"))
      (node (ref "U12") (pin "3") (pinfunction "CATHODE_3") (pintype "passive"))
    )
    (net (code "63") (name "Net-(U13-CATHODE)") (class "Default")
      (node (ref "R33") (pin "2") (pinfunction "2_2") (pintype "passive"))
      (node (ref "U13") (pin "3") (pinfunction "CATHODE_3") (pintype "passive"))
    )
    (net (code "64") (name "Net-(U16-GND)") (class "Default")
      (node (ref "C36") (pin "1") (pinfunction "1_1") (pintype "passive"))
      (node (ref "C37") (pin "2") (pinfunction "2_2") (pintype "passive"))
      (node (ref "C41") (pin "2") (pinfunction "2_2") (pintype "passive"))
      (node (ref "C42") (pin "2") (pinfunction "2_2") (pintype "passive"))
      (node (ref "R38") (pin "1") (pinfunction "1_1") (pintype "passive"))
      (node (ref "U16") (pin "3") (pinfunction "GND_3") (pintype "passive"))
      (node (ref "U19") (pin "3") (pinfunction "Iret_3") (pintype "passive"))
    )
    (net (code "65") (name "Net-(U16-VCC)") (class "Default")
      (node (ref "C36") (pin "2") (pinfunction "2_2") (pintype "passive"))
      (node (ref "C37") (pin "1") (pinfunction "1_1") (pintype "passive"))
      (node (ref "R42") (pin "2") (pinfunction "2_2") (pintype "passive"))
      (node (ref "U15") (pin "4") (pintype "passive"))
      (node (ref "U16") (pin "5") (pinfunction "VCC_5") (pintype "passive"))
    )
    (net (code "66") (name "Net-(U17-CATHODE)") (class "Default")
      (node (ref "R40") (pin "1") (pinfunction "1_1") (pintype "passive"))
      (node (ref "U17") (pin "3") (pinfunction "CATHODE_3") (pintype "passive"))
    )
    (net (code "67") (name "Net-(U19-Iin)") (class "Default")
      (node (ref "R46") (pin "2") (pinfunction "2_2") (pintype "passive"))
      (node (ref "U19") (pin "2") (pinfunction "Iin_2") (pintype "passive"))
    )
    (net (code "68") (name "Net-(U19-Vref)") (class "Default")
      (node (ref "R42") (pin "1") (pinfunction "1_1") (pintype "passive"))
      (node (ref "U19") (pin "1") (pinfunction "Vref_1") (pintype "passive"))
    )
    (net (code "69") (name "Net-(U21-DE)") (class "Default")
      (node (ref "R47") (pin "1") (pinfunction "1_1") (pintype "passive"))
      (node (ref "U20") (pin "3") (pintype "passive"))
      (node (ref "U21") (pin "2") (pinfunction "/RE_2") (pintype "passive"))
      (node (ref "U21") (pin "3") (pinfunction "DE_3") (pintype "passive"))
    )
    (net (code "70") (name "Net-(U21-DI)") (class "Default")
      (node (ref "R49") (pin "1") (pinfunction "1_1") (pintype "passive"))
      (node (ref "U21") (pin "4") (pinfunction "DI_4") (pintype "passive"))
      (node (ref "U22") (pin "6") (pinfunction "VO_6") (pintype "passive"))
    )
    (net (code "71") (name "Net-(U21-RO)") (class "Default")
      (node (ref "R40") (pin "2") (pinfunction "2_2") (pintype "passive"))
      (node (ref "U21") (pin "1") (pinfunction "RO_1") (pintype "passive"))
    )
    (net (code "72") (name "Net-(U22-CATHODE)") (class "Default")
      (node (ref "R50") (pin "2") (pinfunction "2_2") (pintype "passive"))
      (node (ref "U22") (pin "3") (pinfunction "CATHODE_3") (pintype "passive"))
    )
    (net (code "73") (name "P+5V") (class "Default")
      (node (ref "C38") (pin "1") (pinfunction "1_1") (pintype "passive"))
      (node (ref "C39") (pin "2") (pinfunction "2_2") (pintype "passive"))
      (node (ref "R44") (pin "2") (pinfunction "2_2") (pintype "passive"))
      (node (ref "R49") (pin "2") (pinfunction "2_2") (pintype "passive"))
      (node (ref "U17") (pin "2") (pinfunction "ANODE_2") (pintype "passive"))
      (node (ref "U18") (pin "5") (pinfunction "+Vo_5") (pintype "passive"))
      (node (ref "U20") (pin "4") (pintype "passive"))
      (node (ref "U21") (pin "8") (pinfunction "VCC_8") (pintype "power_in"))
      (node (ref "U22") (pin "7") (pinfunction "VE_7") (pintype "passive"))
      (node (ref "U22") (pin "8") (pinfunction "VCC_8") (pintype "passive"))
    )
    (net (code "74") (name "PGND") (class "Default")
      (node (ref "C38") (pin "2") (pinfunction "2_2") (pintype "passive"))
      (node (ref "C39") (pin "1") (pinfunction "1_1") (pintype "passive"))
      (node (ref "FL6") (pin "1") (pinfunction "A_1") (pintype "passive"))
      (node (ref "FL7") (pin "1") (pinfunction "A_1") (pintype "passive"))
      (node (ref "R47") (pin "2") (pinfunction "2_2") (pintype "passive"))
      (node (ref "R48") (pin "2") (pinfunction "2_2") (pintype "passive"))
      (node (ref "U18") (pin "4") (pinfunction "0V_4") (pintype "passive"))
      (node (ref "U21") (pin "5") (pinfunction "GND_5") (pintype "passive"))
      (node (ref "U22") (pin "5") (pinfunction "GND_5") (pintype "passive"))
    )
    (net (code "75") (name "unconnected-(JK1-Pad4)") (class "Default")
      (node (ref "JK1") (pin "4") (pinfunction "4_4") (pintype "passive"))
    )
    (net (code "76") (name "unconnected-(JK2-Pad4)") (class "Default")
      (node (ref "JK2") (pin "4") (pinfunction "4_4") (pintype "passive"))
    )
    (net (code "77") (name "unconnected-(U5-NC-Pad8)") (class "Default")
      (node (ref "U5") (pin "8") (pinfunction "NC_8") (pintype "passive"))
    )
    (net (code "78") (name "unconnected-(U6-NC-Pad1)") (class "Default")
      (node (ref "U6") (pin "1") (pinfunction "NC_1") (pintype "passive"))
    )
    (net (code "79") (name "unconnected-(U6-NC-Pad4)") (class "Default")
      (node (ref "U6") (pin "4") (pinfunction "NC_4") (pintype "passive"))
    )
    (net (code "80") (name "unconnected-(U7-NC-Pad1)") (class "Default")
      (node (ref "U7") (pin "1") (pinfunction "NC_1") (pintype "passive"))
    )
    (net (code "81") (name "unconnected-(U7-NC-Pad4)") (class "Default")
      (node (ref "U7") (pin "4") (pinfunction "NC_4") (pintype "passive"))
    )
    (net (code "82") (name "unconnected-(U12-NC-Pad1)") (class "Default")
      (node (ref "U12") (pin "1") (pinfunction "NC_1") (pintype "passive"))
    )
    (net (code "83") (name "unconnected-(U12-NC-Pad4)") (class "Default")
      (node (ref "U12") (pin "4") (pinfunction "NC_4") (pintype "passive"))
    )
    (net (code "84") (name "unconnected-(U13-GND-Pad5)") (class "Default")
      (node (ref "U13") (pin "5") (pinfunction "GND_5") (pintype "passive"))
    )
    (net (code "85") (name "unconnected-(U13-NC-Pad1)") (class "Default")
      (node (ref "U13") (pin "1") (pinfunction "NC_1") (pintype "passive"))
    )
    (net (code "86") (name "unconnected-(U13-NC-Pad4)") (class "Default")
      (node (ref "U13") (pin "4") (pinfunction "NC_4") (pintype "passive"))
    )
    (net (code "87") (name "unconnected-(U14-NC-Pad8)") (class "Default")
      (node (ref "U14") (pin "8") (pinfunction "NC_8") (pintype "passive"))
    )
    (net (code "88") (name "unconnected-(U16-NC-Pad1)") (class "Default")
      (node (ref "U16") (pin "1") (pinfunction "NC_1") (pintype "passive"))
    )
    (net (code "89") (name "unconnected-(U17-NC-Pad1)") (class "Default")
      (node (ref "U17") (pin "1") (pinfunction "NC_1") (pintype "passive"))
    )
    (net (code "90") (name "unconnected-(U17-NC-Pad4)") (class "Default")
      (node (ref "U17") (pin "4") (pinfunction "NC_4") (pintype "passive"))
    )
    (net (code "91") (name "unconnected-(U18-NC-Pad8)") (class "Default")
      (node (ref "U18") (pin "8") (pinfunction "NC_8") (pintype "passive"))
    )
    (net (code "92") (name "unconnected-(U19-Vreg-Pad8)") (class "Default")
      (node (ref "U19") (pin "8") (pinfunction "Vreg_8") (pintype "passive"))
    )
    (net (code "93") (name "unconnected-(U22-NC-Pad1)") (class "Default")
      (node (ref "U22") (pin "1") (pinfunction "NC_1") (pintype "passive"))
    )
    (net (code "94") (name "unconnected-(U22-NC-Pad4)") (class "Default")
      (node (ref "U22") (pin "4") (pinfunction "NC_4") (pintype "passive"))
    )
  )
)
